# OSO-RING-A1-00.net
KiCad netlist of a schematic drawn in EAGLE
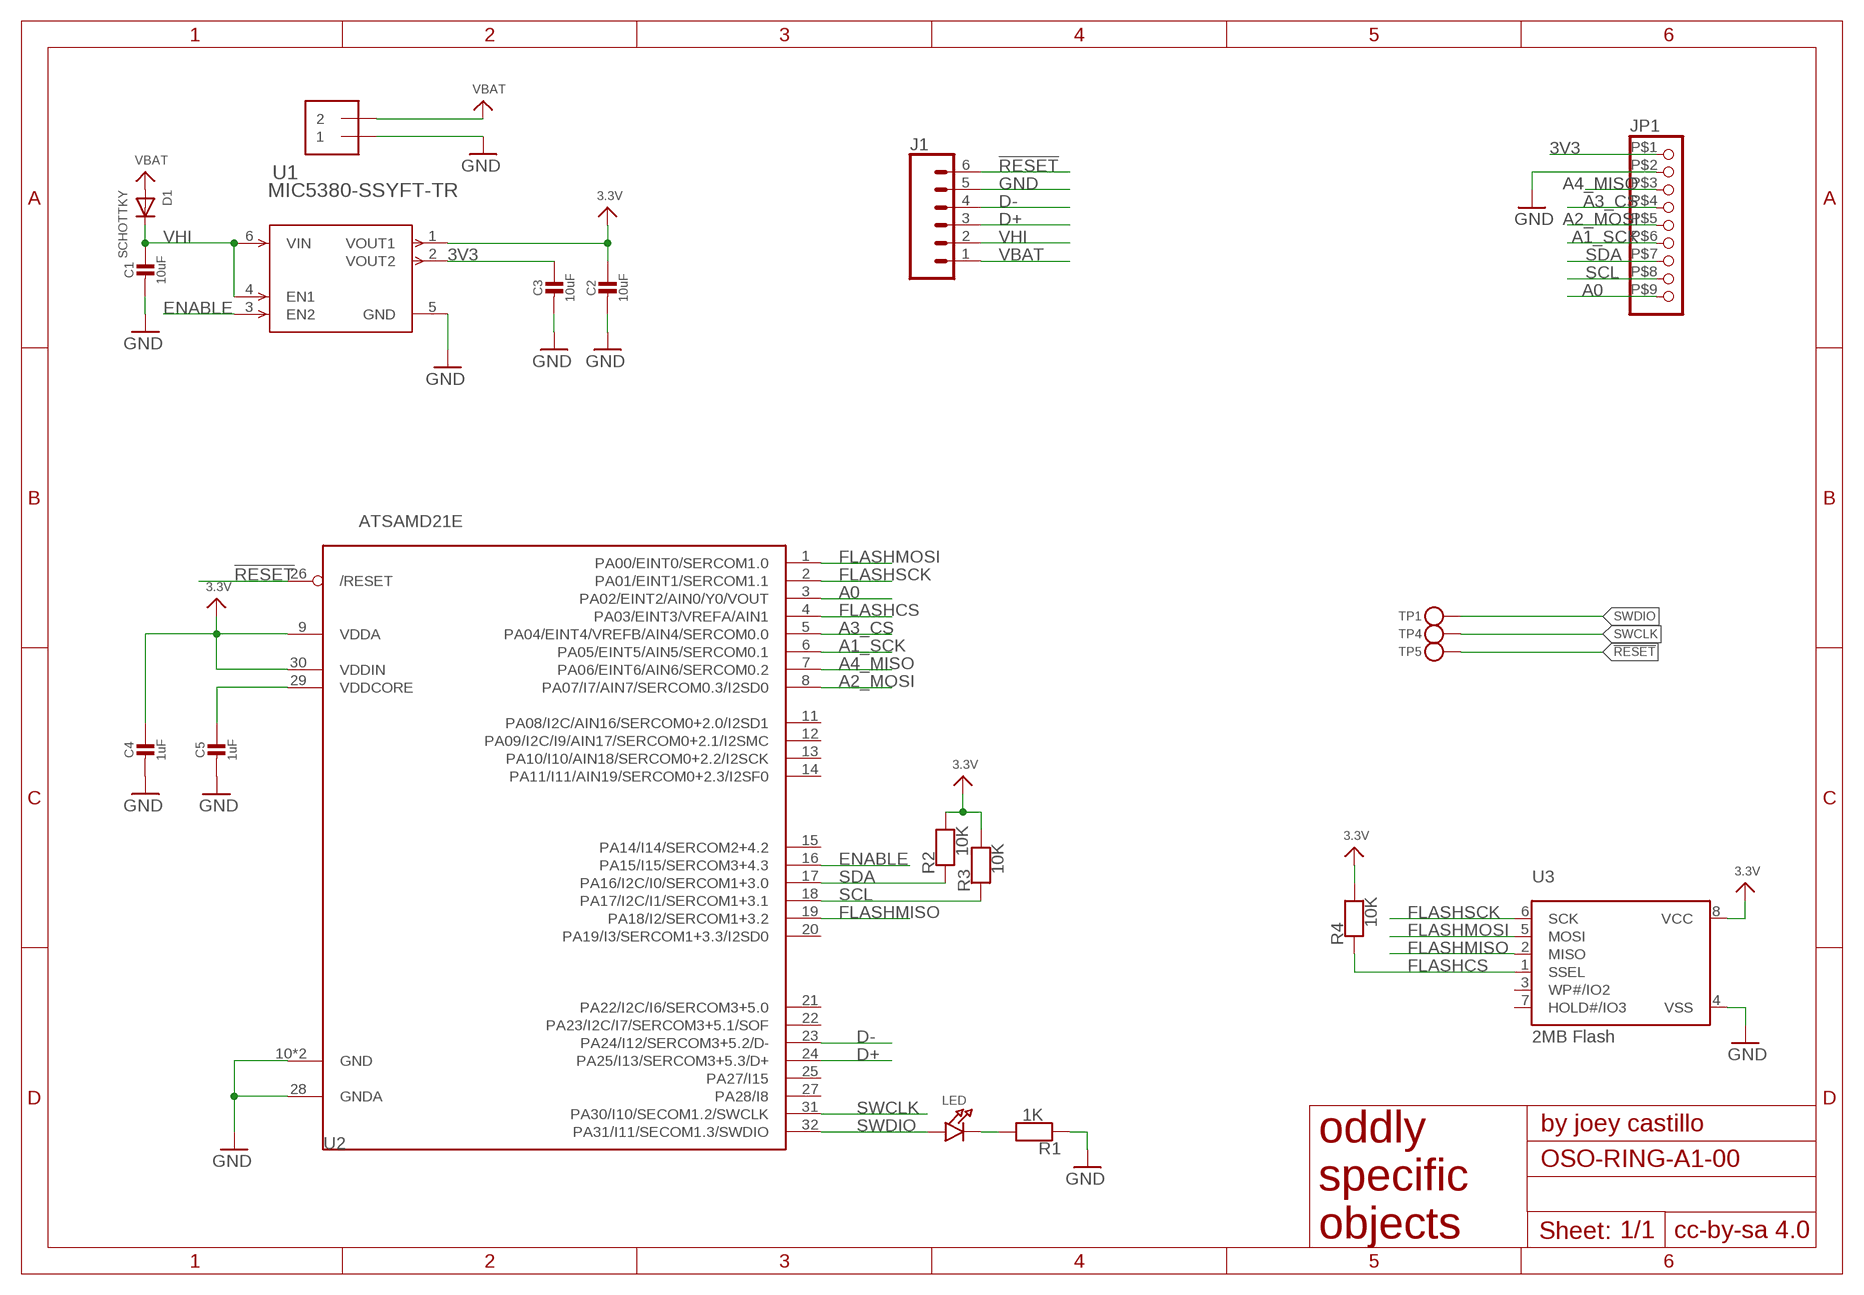
[diagram p0: schematic, sheet 1]

(export (version "E")
  (design (tool "Eeschema 10.0.6"))
  (components
    (comp (ref "C1")
      (value "10uF")
      (footprint "eagle-import:0603-NO")
      (libsource (lib "eagle-import") (part "CAP_CERAMIC0603_NO"))
    )
    (comp (ref "C2")
      (value "10uF")
      (footprint "eagle-import:0603-NO")
      (libsource (lib "eagle-import") (part "CAP_CERAMIC0603_NO"))
    )
    (comp (ref "C3")
      (value "10uF")
      (footprint "eagle-import:0603-NO")
      (libsource (lib "eagle-import") (part "CAP_CERAMIC0603_NO"))
    )
    (comp (ref "C4")
      (value "1uF")
      (footprint "eagle-import:0603-NO")
      (libsource (lib "eagle-import") (part "CAP_CERAMIC0603_NO"))
    )
    (comp (ref "C5")
      (value "1uF")
      (footprint "eagle-import:0603-NO")
      (libsource (lib "eagle-import") (part "CAP_CERAMIC0603_NO"))
    )
    (comp (ref "D1")
      (value "SCHOTTKY")
      (footprint "eagle-import:SOD-123")
      (libsource (lib "eagle-import") (part "DIODESOD-123"))
    )
    (comp (ref "J1")
      (value "CONN_06SMD-1MM")
      (footprint "eagle-import:1X06-1MM")
      (libsource (lib "eagle-import") (part "CONN_06SMD-1MM"))
    )
    (comp (ref "J2")
      (value "1X2SMT")
      (footprint "eagle-import:2PIN_SMT_CONNECTOR")
      (libsource (lib "eagle-import") (part "1X2SMT"))
    )
    (comp (ref "JP1")
      (value "HEADER-1X9BOARD_TO_FLEX")
      (footprint "eagle-import:9PIN_SMT_CONNECTOR")
      (libsource (lib "eagle-import") (part "HEADER-1X9BOARD_TO_FLEX"))
    )
    (comp (ref "LED")
      (value "LED0603_NOOUTLINE")
      (footprint "eagle-import:CHIPLED_0603_NOOUTLINE")
      (libsource (lib "eagle-import") (part "LED0603_NOOUTLINE"))
    )
    (comp (ref "R1")
      (value "1K")
      (footprint "eagle-import:0603-NO")
      (libsource (lib "eagle-import") (part "RESISTOR_0603_NOOUT"))
    )
    (comp (ref "R2")
      (value "10K")
      (footprint "eagle-import:0603-NO")
      (libsource (lib "eagle-import") (part "RESISTOR_0603_NOOUT"))
    )
    (comp (ref "R3")
      (value "10K")
      (footprint "eagle-import:0603-NO")
      (libsource (lib "eagle-import") (part "RESISTOR_0603_NOOUT"))
    )
    (comp (ref "R4")
      (value "10K")
      (footprint "eagle-import:0603-NO")
      (libsource (lib "eagle-import") (part "RESISTOR_0603_NOOUT"))
    )
    (comp (ref "TP1")
      (value "TESTPOINTROUND1.5MMNO")
      (footprint "eagle-import:TESTPOINT_ROUND_1.5MM_NO")
      (libsource (lib "eagle-import") (part "TESTPOINTROUND1.5MMNO"))
    )
    (comp (ref "TP4")
      (value "TESTPOINTROUND1.5MMNO")
      (footprint "eagle-import:TESTPOINT_ROUND_1.5MM_NO")
      (libsource (lib "eagle-import") (part "TESTPOINTROUND1.5MMNO"))
    )
    (comp (ref "TP5")
      (value "TESTPOINTROUND1.5MMNO")
      (footprint "eagle-import:TESTPOINT_ROUND_1.5MM_NO")
      (libsource (lib "eagle-import") (part "TESTPOINTROUND1.5MMNO"))
    )
    (comp (ref "U1")
      (value "MIC5380-SSYFT-TR")
      (footprint "eagle-import:TMLF-6_FT_MCH")
      (fields (field (name "COPYRIGHT") "Copyright (C) 2018 Accelerated Designs. All rights reserved"))
      (libsource (lib "eagle-import") (part "MIC5380-SSYFT-TR"))
    )
    (comp (ref "U2")
      (value "ATSAMD21E")
      (footprint "eagle-import:QFN32_5MM")
      (libsource (lib "eagle-import") (part "ATSAMD21E"))
    )
    (comp (ref "U3")
      (value "2MB Flash")
      (footprint "eagle-import:USON8")
      (libsource (lib "eagle-import") (part "SPIFLASH_8PINUX"))
    )
  )
  (nets
    (net (code "1") (name "/3V3") (class "Default")
      (node (ref "C3") (pin "1") (pinfunction "1_1") (pintype "passive"))
      (node (ref "JP1") (pin "P$1") (pinfunction "1_P$1") (pintype "passive"))
      (node (ref "U1") (pin "2") (pinfunction "VOUT2_2") (pintype "output"))
    )
    (net (code "2") (name "/A0") (class "Default")
      (node (ref "JP1") (pin "P$9") (pinfunction "9_P$9") (pintype "passive"))
      (node (ref "U2") (pin "3") (pinfunction "PA02/EINT2/AIN0/Y0/VOUT_3") (pintype "bidirectional"))
    )
    (net (code "3") (name "/A1_SCK") (class "Default")
      (node (ref "JP1") (pin "P$6") (pinfunction "6_P$6") (pintype "passive"))
      (node (ref "U2") (pin "6") (pinfunction "PA05/EINT5/AIN5/SERCOM0.1_6") (pintype "bidirectional"))
    )
    (net (code "4") (name "/A2_MOSI") (class "Default")
      (node (ref "JP1") (pin "P$5") (pinfunction "5_P$5") (pintype "passive"))
      (node (ref "U2") (pin "8") (pinfunction "PA07/I7/AIN7/SERCOM0.3/I2SD0_8") (pintype "bidirectional"))
    )
    (net (code "5") (name "/A3_CS") (class "Default")
      (node (ref "JP1") (pin "P$4") (pinfunction "4_P$4") (pintype "passive"))
      (node (ref "U2") (pin "5") (pinfunction "PA04/EINT4/VREFB/AIN4/SERCOM0.0_5") (pintype "bidirectional"))
    )
    (net (code "6") (name "/A4_MISO") (class "Default")
      (node (ref "JP1") (pin "P$3") (pinfunction "3_P$3") (pintype "passive"))
      (node (ref "U2") (pin "7") (pinfunction "PA06/EINT6/AIN6/SERCOM0.2_7") (pintype "bidirectional"))
    )
    (net (code "7") (name "/D+") (class "Default")
      (node (ref "J1") (pin "3") (pinfunction "3_3") (pintype "passive"))
      (node (ref "U2") (pin "24") (pinfunction "PA25/I13/SERCOM3+5.3/D+_24") (pintype "bidirectional"))
    )
    (net (code "8") (name "/D-") (class "Default")
      (node (ref "J1") (pin "4") (pinfunction "4_4") (pintype "passive"))
      (node (ref "U2") (pin "23") (pinfunction "PA24/I12/SERCOM3+5.2/D-_23") (pintype "bidirectional"))
    )
    (net (code "9") (name "/ENABLE") (class "Default")
      (node (ref "U1") (pin "3") (pinfunction "EN2_3") (pintype "input"))
      (node (ref "U2") (pin "16") (pinfunction "PA15/I15/SERCOM3+4.3_16") (pintype "bidirectional"))
    )
    (net (code "10") (name "/FLASHCS") (class "Default")
      (node (ref "R4") (pin "1") (pinfunction "1_1") (pintype "passive"))
      (node (ref "U2") (pin "4") (pinfunction "PA03/EINT3/VREFA/AIN1_4") (pintype "bidirectional"))
      (node (ref "U3") (pin "1") (pinfunction "SSEL_1") (pintype "bidirectional"))
    )
    (net (code "11") (name "/FLASHMISO") (class "Default")
      (node (ref "U2") (pin "19") (pinfunction "PA18/I2/SERCOM1+3.2_19") (pintype "bidirectional"))
      (node (ref "U3") (pin "2") (pinfunction "MISO_2") (pintype "bidirectional"))
    )
    (net (code "12") (name "/FLASHMOSI") (class "Default")
      (node (ref "U2") (pin "1") (pinfunction "PA00/EINT0/SERCOM1.0_1") (pintype "bidirectional"))
      (node (ref "U3") (pin "5") (pinfunction "MOSI_5") (pintype "bidirectional"))
    )
    (net (code "13") (name "/FLASHSCK") (class "Default")
      (node (ref "U2") (pin "2") (pinfunction "PA01/EINT1/SERCOM1.1_2") (pintype "bidirectional"))
      (node (ref "U3") (pin "6") (pinfunction "SCK_6") (pintype "bidirectional"))
    )
    (net (code "14") (name "/SCL") (class "Default")
      (node (ref "JP1") (pin "P$8") (pinfunction "8_P$8") (pintype "passive"))
      (node (ref "R3") (pin "1") (pinfunction "1_1") (pintype "passive"))
      (node (ref "U2") (pin "18") (pinfunction "PA17/I2C/I1/SERCOM1+3.1_18") (pintype "bidirectional"))
    )
    (net (code "15") (name "/SDA") (class "Default")
      (node (ref "JP1") (pin "P$7") (pinfunction "7_P$7") (pintype "passive"))
      (node (ref "R2") (pin "1") (pinfunction "1_1") (pintype "passive"))
      (node (ref "U2") (pin "17") (pinfunction "PA16/I2C/I0/SERCOM1+3.0_17") (pintype "bidirectional"))
    )
    (net (code "16") (name "/VHI") (class "Default")
      (node (ref "C1") (pin "1") (pinfunction "1_1") (pintype "passive"))
      (node (ref "D1") (pin "C") (pinfunction "C_C") (pintype "passive"))
      (node (ref "J1") (pin "2") (pinfunction "2_2") (pintype "passive"))
      (node (ref "U1") (pin "4") (pinfunction "EN1_4") (pintype "input"))
      (node (ref "U1") (pin "6") (pinfunction "VIN_6") (pintype "input"))
    )
    (net (code "17") (name "/~{RESET}") (class "Default")
      (node (ref "J1") (pin "6") (pinfunction "6_6") (pintype "passive"))
      (node (ref "TP5") (pin "P$1") (pinfunction "P$1_P$1") (pintype "bidirectional"))
      (node (ref "U2") (pin "26") (pinfunction "/RESET_26") (pintype "bidirectional"))
    )
    (net (code "18") (name "3.3V") (class "Default")
      (node (ref "C2") (pin "1") (pinfunction "1_1") (pintype "passive"))
      (node (ref "C4") (pin "1") (pinfunction "1_1") (pintype "passive"))
      (node (ref "R2") (pin "2") (pinfunction "2_2") (pintype "passive"))
      (node (ref "R3") (pin "2") (pinfunction "2_2") (pintype "passive"))
      (node (ref "R4") (pin "2") (pinfunction "2_2") (pintype "passive"))
      (node (ref "U1") (pin "1") (pinfunction "VOUT1_1") (pintype "output"))
      (node (ref "U2") (pin "30") (pinfunction "VDDIN_30") (pintype "power_in"))
      (node (ref "U2") (pin "9") (pinfunction "VDDA_9") (pintype "power_in"))
      (node (ref "U3") (pin "8") (pinfunction "VCC_8") (pintype "bidirectional"))
    )
    (net (code "19") (name "GND") (class "Default")
      (node (ref "C1") (pin "2") (pinfunction "2_2") (pintype "passive"))
      (node (ref "C2") (pin "2") (pinfunction "2_2") (pintype "passive"))
      (node (ref "C3") (pin "2") (pinfunction "2_2") (pintype "passive"))
      (node (ref "C4") (pin "2") (pinfunction "2_2") (pintype "passive"))
      (node (ref "C5") (pin "2") (pinfunction "2_2") (pintype "passive"))
      (node (ref "J1") (pin "5") (pinfunction "5_5") (pintype "passive"))
      (node (ref "J2") (pin "P$1") (pinfunction "1_P$1") (pintype "passive"))
      (node (ref "JP1") (pin "P$2") (pinfunction "2_P$2") (pintype "passive"))
      (node (ref "R1") (pin "1") (pinfunction "1_1") (pintype "passive"))
      (node (ref "U1") (pin "5") (pinfunction "GND_5") (pintype "power_in"))
      (node (ref "U2") (pin "10") (pinfunction "GND_10") (pintype "power_in"))
      (node (ref "U2") (pin "28") (pinfunction "GNDA_28") (pintype "power_in"))
      (node (ref "U2") (pin "33") (pinfunction "GND_33") (pintype "power_in"))
      (node (ref "U3") (pin "4") (pinfunction "VSS_4") (pintype "bidirectional"))
    )
    (net (code "20") (name "Net-(LED-PadC)") (class "Default")
      (node (ref "LED") (pin "C") (pinfunction "C_C") (pintype "passive"))
      (node (ref "R1") (pin "2") (pinfunction "2_2") (pintype "passive"))
    )
    (net (code "21") (name "Net-(U2-VDDCORE)") (class "Default")
      (node (ref "C5") (pin "1") (pinfunction "1_1") (pintype "passive"))
      (node (ref "U2") (pin "29") (pinfunction "VDDCORE_29") (pintype "power_in"))
    )
    (net (code "22") (name "SWCLK") (class "Default")
      (node (ref "TP4") (pin "P$1") (pinfunction "P$1_P$1") (pintype "bidirectional"))
      (node (ref "U2") (pin "31") (pinfunction "PA30/I10/SECOM1.2/SWCLK_31") (pintype "bidirectional"))
    )
    (net (code "23") (name "SWDIO") (class "Default")
      (node (ref "LED") (pin "A") (pinfunction "A_A") (pintype "passive"))
      (node (ref "TP1") (pin "P$1") (pinfunction "P$1_P$1") (pintype "bidirectional"))
      (node (ref "U2") (pin "32") (pinfunction "PA31/I11/SECOM1.3/SWDIO_32") (pintype "bidirectional"))
    )
    (net (code "24") (name "VBAT") (class "Default")
      (node (ref "D1") (pin "A") (pinfunction "A_A") (pintype "passive"))
      (node (ref "J1") (pin "1") (pinfunction "1_1") (pintype "passive"))
      (node (ref "J2") (pin "P$2") (pinfunction "2_P$2") (pintype "passive"))
    )
    (net (code "25") (name "unconnected-(U2-PA08{slash}I2C{slash}AIN16{slash}SERCOM0+2.0{slash}I2SD1-Pad11)") (class "Default")
      (node (ref "U2") (pin "11") (pinfunction "PA08/I2C/AIN16/SERCOM0+2.0/I2SD1_11") (pintype "bidirectional"))
    )
    (net (code "26") (name "unconnected-(U2-PA09{slash}I2C{slash}I9{slash}AIN17{slash}SERCOM0+2.1{slash}I2SMC-Pad12)") (class "Default")
      (node (ref "U2") (pin "12") (pinfunction "PA09/I2C/I9/AIN17/SERCOM0+2.1/I2SMC_12") (pintype "bidirectional"))
    )
    (net (code "27") (name "unconnected-(U2-PA10{slash}I10{slash}AIN18{slash}SERCOM0+2.2{slash}I2SCK-Pad13)") (class "Default")
      (node (ref "U2") (pin "13") (pinfunction "PA10/I10/AIN18/SERCOM0+2.2/I2SCK_13") (pintype "bidirectional"))
    )
    (net (code "28") (name "unconnected-(U2-PA11{slash}I11{slash}AIN19{slash}SERCOM0+2.3{slash}I2SF0-Pad14)") (class "Default")
      (node (ref "U2") (pin "14") (pinfunction "PA11/I11/AIN19/SERCOM0+2.3/I2SF0_14") (pintype "bidirectional"))
    )
    (net (code "29") (name "unconnected-(U2-PA14{slash}I14{slash}SERCOM2+4.2-Pad15)") (class "Default")
      (node (ref "U2") (pin "15") (pinfunction "PA14/I14/SERCOM2+4.2_15") (pintype "bidirectional"))
    )
    (net (code "30") (name "unconnected-(U2-PA19{slash}I3{slash}SERCOM1+3.3{slash}I2SD0-Pad20)") (class "Default")
      (node (ref "U2") (pin "20") (pinfunction "PA19/I3/SERCOM1+3.3/I2SD0_20") (pintype "bidirectional"))
    )
    (net (code "31") (name "unconnected-(U2-PA22{slash}I2C{slash}I6{slash}SERCOM3+5.0-Pad21)") (class "Default")
      (node (ref "U2") (pin "21") (pinfunction "PA22/I2C/I6/SERCOM3+5.0_21") (pintype "bidirectional"))
    )
    (net (code "32") (name "unconnected-(U2-PA23{slash}I2C{slash}I7{slash}SERCOM3+5.1{slash}SOF-Pad22)") (class "Default")
      (node (ref "U2") (pin "22") (pinfunction "PA23/I2C/I7/SERCOM3+5.1/SOF_22") (pintype "bidirectional"))
    )
    (net (code "33") (name "unconnected-(U2-PA27{slash}I15-Pad25)") (class "Default")
      (node (ref "U2") (pin "25") (pinfunction "PA27/I15_25") (pintype "bidirectional"))
    )
    (net (code "34") (name "unconnected-(U2-PA28{slash}I8-Pad27)") (class "Default")
      (node (ref "U2") (pin "27") (pinfunction "PA28/I8_27") (pintype "bidirectional"))
    )
    (net (code "35") (name "unconnected-(U3-HOLD#{slash}IO3-Pad7)") (class "Default")
      (node (ref "U3") (pin "7") (pinfunction "HOLD#/IO3_7") (pintype "bidirectional"))
    )
    (net (code "36") (name "unconnected-(U3-WP#{slash}IO2-Pad3)") (class "Default")
      (node (ref "U3") (pin "3") (pinfunction "WP#/IO2_3") (pintype "bidirectional"))
    )
  )
)
